# Intercomm_sheet_3.net
KiCad netlist of a schematic drawn in Altium Designer
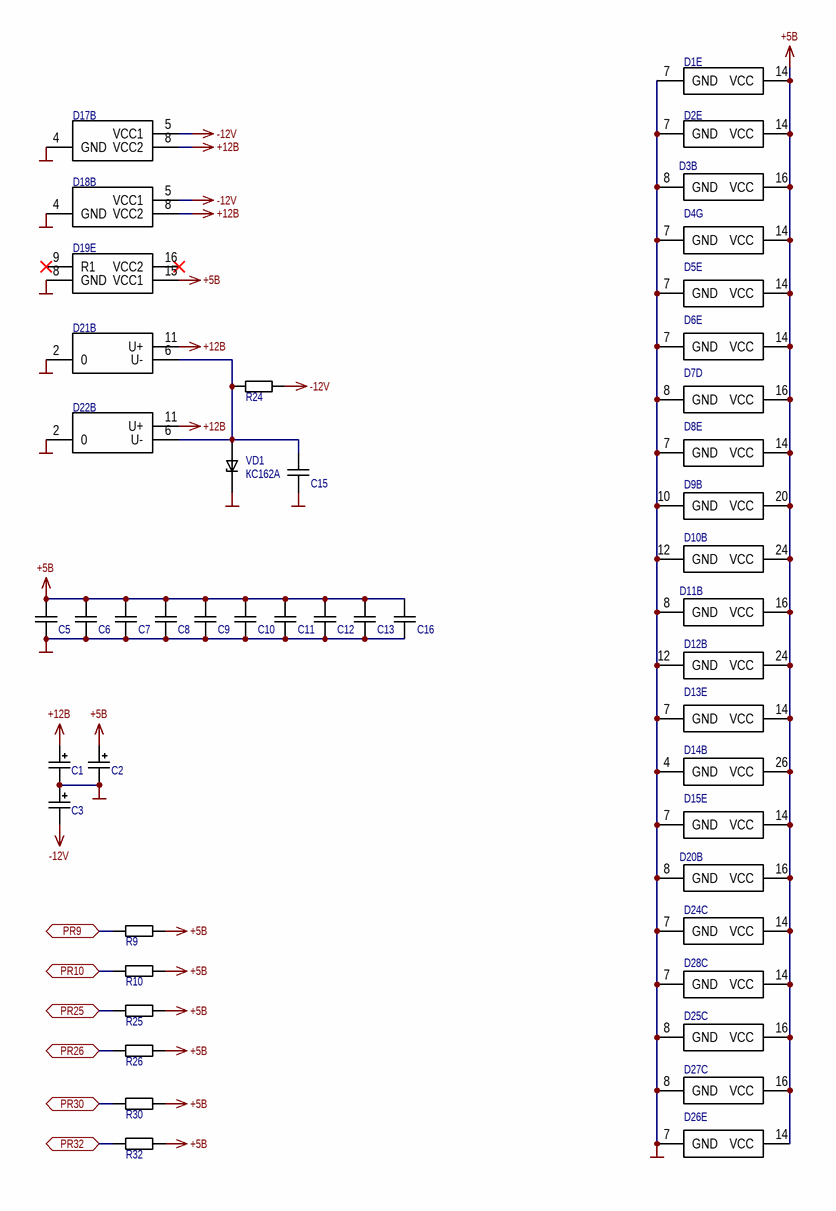
[diagram p0: Intercomm_sheet_3.SchDoc]

(export (version "E")
  (design (tool "Eeschema 10.0.6"))
  (components
    (comp (ref "C1")
      (value "0,1")
      (footprint "CP25")
      (description "К53-14")
      (libsource (lib "Agat") (part "К53-14"))
    )
    (comp (ref "C2")
      (value "0,1")
      (footprint "CP25")
      (description "К53-14")
      (libsource (lib "Agat") (part "К53-14"))
    )
    (comp (ref "C3")
      (value "0,1")
      (footprint "CP25")
      (description "К53-14")
      (libsource (lib "Agat") (part "К53-14"))
    )
    (comp (ref "C5")
      (value "0,1")
      (footprint "C5")
      (description "К10-17")
      (libsource (lib "Agat") (part "К10-17"))
    )
    (comp (ref "C6")
      (value "0,1")
      (footprint "C5")
      (description "К10-17")
      (libsource (lib "Agat") (part "К10-17"))
    )
    (comp (ref "C7")
      (value "0,1")
      (footprint "C5")
      (description "К10-17")
      (libsource (lib "Agat") (part "К10-17"))
    )
    (comp (ref "C8")
      (value "0,1")
      (footprint "C5")
      (description "К10-17")
      (libsource (lib "Agat") (part "К10-17"))
    )
    (comp (ref "C9")
      (value "0,1")
      (footprint "C5")
      (description "К10-17")
      (libsource (lib "Agat") (part "К10-17"))
    )
    (comp (ref "C10")
      (value "0,1")
      (footprint "C5")
      (description "К10-17")
      (libsource (lib "Agat") (part "К10-17"))
    )
    (comp (ref "C11")
      (value "0,1")
      (footprint "C5")
      (description "К10-17")
      (libsource (lib "Agat") (part "К10-17"))
    )
    (comp (ref "C12")
      (value "0,1")
      (footprint "C5")
      (description "К10-17")
      (libsource (lib "Agat") (part "К10-17"))
    )
    (comp (ref "C13")
      (value "0,1")
      (footprint "C5")
      (description "К10-17")
      (libsource (lib "Agat") (part "К10-17"))
    )
    (comp (ref "C15")
      (value "0,1")
      (footprint "C5")
      (description "К10-17")
      (libsource (lib "Agat") (part "К10-17"))
    )
    (comp (ref "C16")
      (value "0,1")
      (footprint "C5")
      (description "К10-17")
      (libsource (lib "Agat") (part "К10-17"))
    )
    (comp (ref "D1") (value "К555ЛП8") (footprint "201.14") (libsource (lib "Agat") (part "К555ЛП8")))
    (comp (ref "D2") (value "К555ЛП8") (footprint "201.14") (libsource (lib "Agat") (part "К555ЛП8")))
    (comp (ref "D3") (value "К555ИД4") (footprint "201.16") (libsource (lib "Agat") (part "К555ИД4")))
    (comp (ref "D4") (value "К555ТЛ2") (footprint "201.14") (libsource (lib "Agat") (part "К555ТЛ2")))
    (comp (ref "D5") (value "К555ЛИ1") (footprint "201.14") (libsource (lib "Agat") (part "К555ЛИ1")))
    (comp (ref "D6") (value "К555ЛА3") (footprint "201.14") (libsource (lib "Agat") (part "К555ЛА3")))
    (comp (ref "D7")
      (value "КР559ИП7")
      (footprint "201.16")
      (fields (field (name "MANUFACTURERPARTNUMBER") "К555ЛА3"))
      (libsource (lib "Agat") (part "КР559ИП7"))
    )
    (comp (ref "D8")
      (value "К555ЛЕ1")
      (footprint "201.14")
      (fields (field (name "MANUFACTURERPARTNUMBER") "К555ЛА3"))
      (libsource (lib "Agat") (part "К555ЛЕ1"))
    )
    (comp (ref "D9") (value "КР580ВА86") (footprint "2140.20") (libsource (lib "Agat") (part "КР580ВА86_1")))
    (comp (ref "D10")
      (value "К573РФ2")
      (footprint "2120.24 socket")
      (libsource (lib "Agat") (part "К573РФ2"))
    )
    (comp (ref "D11") (value "К555КП11") (footprint "201.16") (libsource (lib "Agat") (part "К555КП11")))
    (comp (ref "D12") (value "КР580ВИ53") (footprint "2120.24") (libsource (lib "Agat") (part "КР580ВИ53")))
    (comp (ref "D13") (value "К555ЛП8") (footprint "201.14") (libsource (lib "Agat") (part "К555ЛП8")))
    (comp (ref "D14") (value "КР580ВВ51А") (footprint "2121.28") (libsource (lib "Agat") (part "КР580ВВ51А")))
    (comp (ref "D15")
      (value "К555ЛЕ1")
      (footprint "201.14")
      (fields (field (name "MANUFACTURERPARTNUMBER") "К555ЛА3"))
      (libsource (lib "Agat") (part "К555ЛЕ1"))
    )
    (comp (ref "D17") (value "К170АП2") (footprint "2101.8") (libsource (lib "Agat") (part "К170АП2")))
    (comp (ref "D18") (value "К170АП2") (footprint "2101.8") (libsource (lib "Agat") (part "К170АП2")))
    (comp (ref "D19") (value "К170УП2") (footprint "201.16") (libsource (lib "Agat") (part "К170УП2")))
    (comp (ref "D20") (value "К555КП11") (footprint "201.16") (libsource (lib "Agat") (part "К555КП11")))
    (comp (ref "D21") (value "К554СА2") (footprint "201.14") (libsource (lib "Agat") (part "К554СА2")))
    (comp (ref "D22") (value "К554СА2") (footprint "201.14") (libsource (lib "Agat") (part "К554СА2")))
    (comp (ref "D24") (value "К555ТМ2") (footprint "201.14") (libsource (lib "Agat") (part "К555ТМ2")))
    (comp (ref "D25") (value "К155АГ3") (footprint "201.16") (libsource (lib "Agat") (part "К155АГ3")))
    (comp (ref "D26") (value "К555ЛА3") (footprint "201.14") (libsource (lib "Agat") (part "К555ЛА3")))
    (comp (ref "D27") (value "К155АГ3") (footprint "201.16") (libsource (lib "Agat") (part "К155АГ3")))
    (comp (ref "D28") (value "К555ТМ2") (footprint "201.14") (libsource (lib "Agat") (part "К555ТМ2")))
    (comp (ref "R9")
      (value "1K")
      (footprint "R10")
      (description "Резистор")
      (libsource (lib "Agat") (part "С2-23"))
    )
    (comp (ref "R10")
      (value "1K")
      (footprint "R10")
      (description "Резистор")
      (libsource (lib "Agat") (part "С2-23"))
    )
    (comp (ref "R24")
      (value "1K")
      (footprint "R10")
      (description "Резистор")
      (libsource (lib "") (part "С2-23_1"))
    )
    (comp (ref "R25")
      (value "1K")
      (footprint "R10")
      (description "Резистор")
      (libsource (lib "Agat") (part "С2-23"))
    )
    (comp (ref "R26")
      (value "1K")
      (footprint "R10")
      (description "Резистор")
      (libsource (lib "Agat") (part "С2-23"))
    )
    (comp (ref "R30")
      (value "1K")
      (footprint "R10")
      (description "Резистор")
      (libsource (lib "Agat") (part "С2-23"))
    )
    (comp (ref "R32")
      (value "1K")
      (footprint "R10")
      (description "Резистор")
      (libsource (lib "Agat") (part "С2-23"))
    )
    (comp (ref "VD1") (value "КС162А") (footprint "КД-25") (libsource (lib "Agat") (part "КС162А")))
  )
  (nets
    (net (code "1") (name "+5В") (class "Default")
      (node (ref "C10") (pin "1") (pintype "passive"))
      (node (ref "C11") (pin "1") (pintype "passive"))
      (node (ref "C12") (pin "1") (pintype "passive"))
      (node (ref "C13") (pin "1") (pintype "passive"))
      (node (ref "C16") (pin "1") (pintype "passive"))
      (node (ref "C2") (pin "1") (pintype "passive"))
      (node (ref "C5") (pin "1") (pintype "passive"))
      (node (ref "C6") (pin "1") (pintype "passive"))
      (node (ref "C7") (pin "1") (pintype "passive"))
      (node (ref "C8") (pin "1") (pintype "passive"))
      (node (ref "C9") (pin "1") (pintype "passive"))
      (node (ref "D1") (pin "14") (pinfunction "VCC_14") (pintype "passive"))
      (node (ref "D10") (pin "24") (pinfunction "VCC_24") (pintype "passive"))
      (node (ref "D11") (pin "16") (pinfunction "VCC_16") (pintype "passive"))
      (node (ref "D12") (pin "24") (pinfunction "VCC_24") (pintype "passive"))
      (node (ref "D13") (pin "14") (pinfunction "VCC_14") (pintype "passive"))
      (node (ref "D14") (pin "26") (pinfunction "VCC_26") (pintype "passive"))
      (node (ref "D15") (pin "14") (pinfunction "VCC_14") (pintype "passive"))
      (node (ref "D19") (pin "15") (pinfunction "VCC1_15") (pintype "passive"))
      (node (ref "D2") (pin "14") (pinfunction "VCC_14") (pintype "passive"))
      (node (ref "D20") (pin "16") (pinfunction "VCC_16") (pintype "passive"))
      (node (ref "D24") (pin "14") (pinfunction "VCC_14") (pintype "passive"))
      (node (ref "D25") (pin "16") (pinfunction "VCC_16") (pintype "passive"))
      (node (ref "D26") (pin "14") (pinfunction "VCC_14") (pintype "passive"))
      (node (ref "D27") (pin "16") (pinfunction "VCC_16") (pintype "passive"))
      (node (ref "D28") (pin "14") (pinfunction "VCC_14") (pintype "passive"))
      (node (ref "D3") (pin "16") (pinfunction "VCC_16") (pintype "passive"))
      (node (ref "D4") (pin "14") (pinfunction "VCC_14") (pintype "passive"))
      (node (ref "D5") (pin "14") (pinfunction "VCC_14") (pintype "passive"))
      (node (ref "D6") (pin "14") (pinfunction "VCC_14") (pintype "passive"))
      (node (ref "D7") (pin "16") (pinfunction "VCC_16") (pintype "passive"))
      (node (ref "D8") (pin "14") (pinfunction "VCC_14") (pintype "passive"))
      (node (ref "D9") (pin "20") (pinfunction "VCC_20") (pintype "passive"))
      (node (ref "R10") (pin "2") (pinfunction "2_2") (pintype "passive"))
      (node (ref "R25") (pin "2") (pinfunction "2_2") (pintype "passive"))
      (node (ref "R26") (pin "2") (pinfunction "2_2") (pintype "passive"))
      (node (ref "R30") (pin "2") (pinfunction "2_2") (pintype "passive"))
      (node (ref "R32") (pin "2") (pinfunction "2_2") (pintype "passive"))
      (node (ref "R9") (pin "2") (pinfunction "2_2") (pintype "passive"))
    )
    (net (code "2") (name "+12В") (class "Default")
      (node (ref "C1") (pin "1") (pintype "passive"))
      (node (ref "D17") (pin "8") (pinfunction "VCC2_8") (pintype "passive"))
      (node (ref "D18") (pin "8") (pinfunction "VCC2_8") (pintype "passive"))
      (node (ref "D21") (pin "11") (pinfunction "U+_11") (pintype "passive"))
      (node (ref "D22") (pin "11") (pinfunction "U+_11") (pintype "passive"))
    )
    (net (code "3") (name "-12V") (class "Default")
      (node (ref "C3") (pin "2") (pintype "passive"))
      (node (ref "D17") (pin "5") (pinfunction "VCC1_5") (pintype "passive"))
      (node (ref "D18") (pin "5") (pinfunction "VCC1_5") (pintype "passive"))
      (node (ref "R24") (pin "1") (pinfunction "1_1") (pintype "passive"))
    )
    (net (code "4") (name "/PR9") (class "Default")
      (node (ref "R9") (pin "1") (pinfunction "1_1") (pintype "passive"))
    )
    (net (code "5") (name "/PR10") (class "Default")
      (node (ref "R10") (pin "1") (pinfunction "1_1") (pintype "passive"))
    )
    (net (code "6") (name "/PR25") (class "Default")
      (node (ref "R25") (pin "1") (pinfunction "1_1") (pintype "passive"))
    )
    (net (code "7") (name "/PR26") (class "Default")
      (node (ref "R26") (pin "1") (pinfunction "1_1") (pintype "passive"))
    )
    (net (code "8") (name "/PR30") (class "Default")
      (node (ref "R30") (pin "1") (pinfunction "1_1") (pintype "passive"))
    )
    (net (code "9") (name "/PR32") (class "Default")
      (node (ref "R32") (pin "1") (pinfunction "1_1") (pintype "passive"))
    )
    (net (code "10") (name "GND") (class "Default")
      (node (ref "C1") (pin "2") (pintype "passive"))
      (node (ref "C10") (pin "2") (pintype "passive"))
      (node (ref "C11") (pin "2") (pintype "passive"))
      (node (ref "C12") (pin "2") (pintype "passive"))
      (node (ref "C13") (pin "2") (pintype "passive"))
      (node (ref "C15") (pin "1") (pintype "passive"))
      (node (ref "C16") (pin "2") (pintype "passive"))
      (node (ref "C2") (pin "2") (pintype "passive"))
      (node (ref "C3") (pin "1") (pintype "passive"))
      (node (ref "C5") (pin "2") (pintype "passive"))
      (node (ref "C6") (pin "2") (pintype "passive"))
      (node (ref "C7") (pin "2") (pintype "passive"))
      (node (ref "C8") (pin "2") (pintype "passive"))
      (node (ref "C9") (pin "2") (pintype "passive"))
      (node (ref "D1") (pin "7") (pinfunction "GND_7") (pintype "passive"))
      (node (ref "D10") (pin "12") (pinfunction "GND_12") (pintype "passive"))
      (node (ref "D11") (pin "8") (pinfunction "GND_8") (pintype "passive"))
      (node (ref "D12") (pin "12") (pinfunction "GND_12") (pintype "passive"))
      (node (ref "D13") (pin "7") (pinfunction "GND_7") (pintype "passive"))
      (node (ref "D14") (pin "4") (pinfunction "GND_4") (pintype "passive"))
      (node (ref "D15") (pin "7") (pinfunction "GND_7") (pintype "passive"))
      (node (ref "D17") (pin "4") (pinfunction "GND_4") (pintype "passive"))
      (node (ref "D18") (pin "4") (pinfunction "GND_4") (pintype "passive"))
      (node (ref "D19") (pin "8") (pinfunction "GND_8") (pintype "passive"))
      (node (ref "D2") (pin "7") (pinfunction "GND_7") (pintype "passive"))
      (node (ref "D20") (pin "8") (pinfunction "GND_8") (pintype "passive"))
      (node (ref "D21") (pin "2") (pinfunction "0_2") (pintype "passive"))
      (node (ref "D22") (pin "2") (pinfunction "0_2") (pintype "passive"))
      (node (ref "D24") (pin "7") (pinfunction "GND_7") (pintype "passive"))
      (node (ref "D25") (pin "8") (pinfunction "GND_8") (pintype "passive"))
      (node (ref "D26") (pin "7") (pinfunction "GND_7") (pintype "passive"))
      (node (ref "D27") (pin "8") (pinfunction "GND_8") (pintype "passive"))
      (node (ref "D28") (pin "7") (pinfunction "GND_7") (pintype "passive"))
      (node (ref "D3") (pin "8") (pinfunction "GND_8") (pintype "passive"))
      (node (ref "D4") (pin "7") (pinfunction "GND_7") (pintype "passive"))
      (node (ref "D5") (pin "7") (pinfunction "GND_7") (pintype "passive"))
      (node (ref "D6") (pin "7") (pinfunction "GND_7") (pintype "passive"))
      (node (ref "D7") (pin "8") (pinfunction "GND_8") (pintype "passive"))
      (node (ref "D8") (pin "7") (pinfunction "GND_7") (pintype "passive"))
      (node (ref "D9") (pin "10") (pinfunction "GND_10") (pintype "passive"))
      (node (ref "VD1") (pin "2") (pinfunction "2_2") (pintype "passive"))
    )
    (net (code "11") (name "Net-(D21B-U-)") (class "Default")
      (node (ref "C15") (pin "2") (pintype "passive"))
      (node (ref "D21") (pin "6") (pinfunction "U-_6") (pintype "passive"))
      (node (ref "D22") (pin "6") (pinfunction "U-_6") (pintype "passive"))
      (node (ref "R24") (pin "2") (pinfunction "2_2") (pintype "passive"))
      (node (ref "VD1") (pin "1") (pinfunction "1_1") (pintype "passive"))
    )
    (net (code "12") (name "unconnected-(D19E-R1-Pad9)") (class "Default")
      (node (ref "D19") (pin "9") (pinfunction "R1_9") (pintype "passive+no_connect"))
    )
    (net (code "13") (name "unconnected-(D19E-VCC2-Pad16)") (class "Default")
      (node (ref "D19") (pin "16") (pinfunction "VCC2_16") (pintype "passive+no_connect"))
    )
  )
)
